# GS_01_Pow.net
KiCad netlist of a schematic drawn in Altium Designer
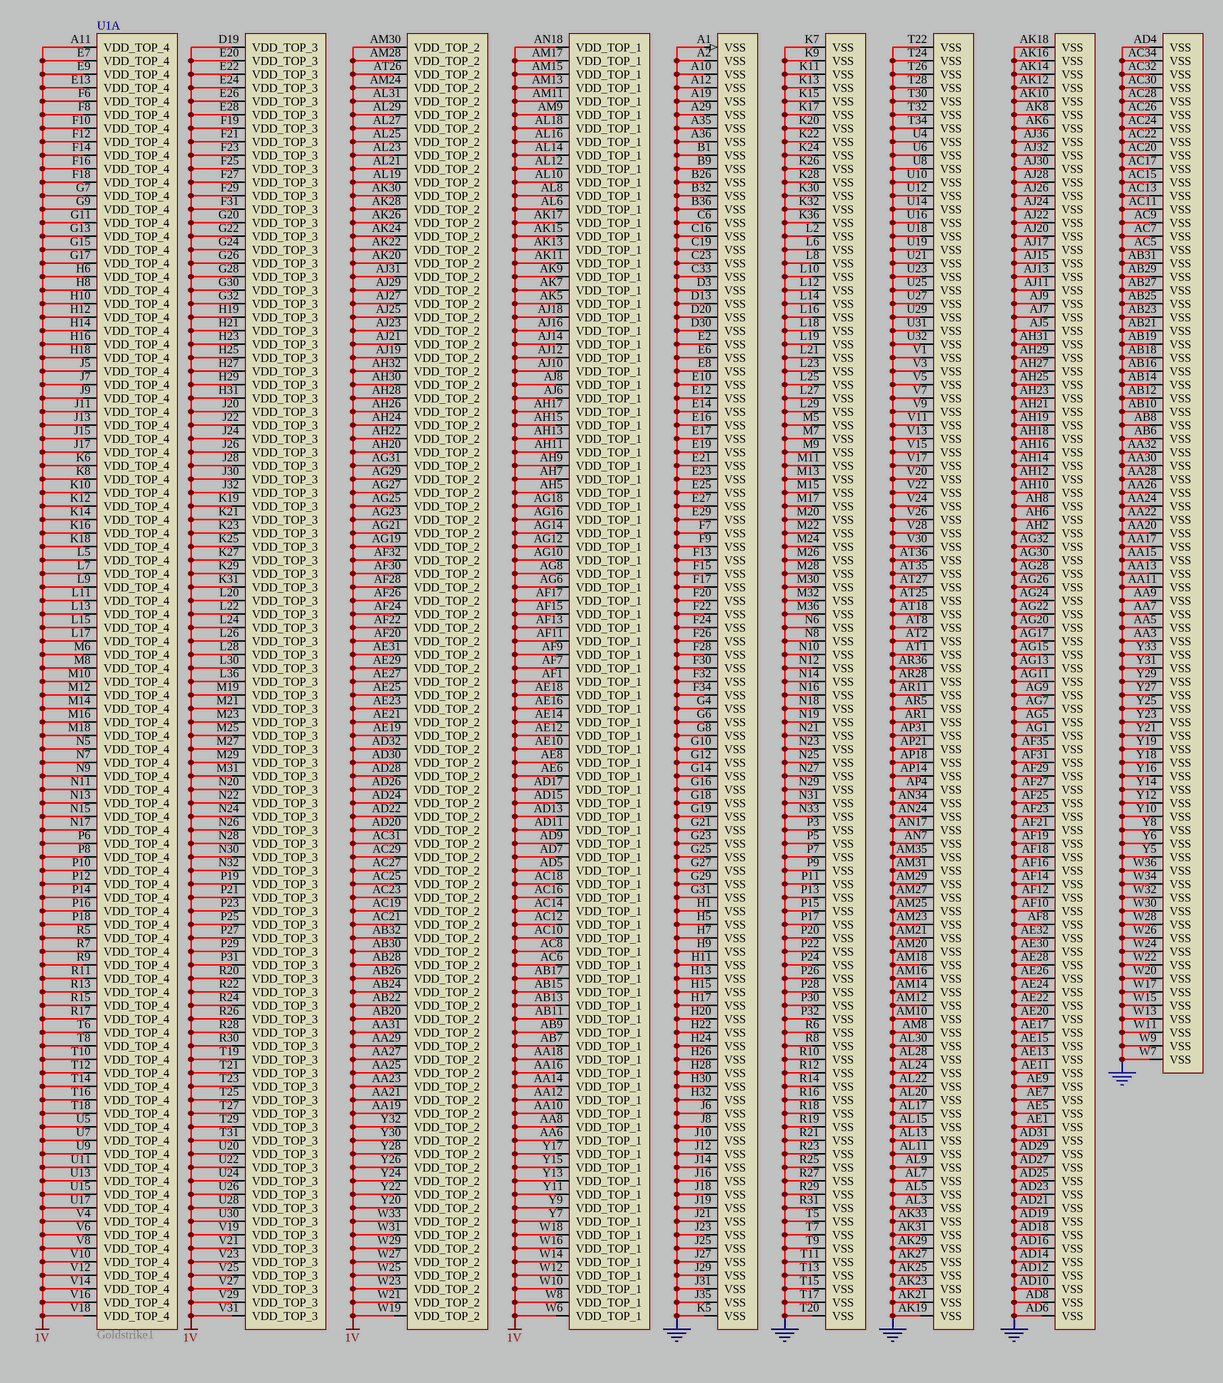
[diagram p0: GS_01_Pow.SchDoc]

(export (version "E")
  (design (tool "Eeschema 10.0.6"))
  (components (comp (ref "U1") (value "Goldstrike1") (libsource (lib "Schlib1") (part "Goldstrike1"))))
  (nets
    (net (code "1") (name "1V") (class "Default")
      (node (ref "U1") (pin "A11") (pinfunction "VDD_TOP_4_A11") (pintype "passive"))
      (node (ref "U1") (pin "AA10") (pinfunction "VDD_TOP_1_AA10") (pintype "passive"))
      (node (ref "U1") (pin "AA12") (pinfunction "VDD_TOP_1_AA12") (pintype "passive"))
      (node (ref "U1") (pin "AA14") (pinfunction "VDD_TOP_1_AA14") (pintype "passive"))
      (node (ref "U1") (pin "AA16") (pinfunction "VDD_TOP_1_AA16") (pintype "passive"))
      (node (ref "U1") (pin "AA18") (pinfunction "VDD_TOP_1_AA18") (pintype "passive"))
      (node (ref "U1") (pin "AA19") (pinfunction "VDD_TOP_2_AA19") (pintype "passive"))
      (node (ref "U1") (pin "AA21") (pinfunction "VDD_TOP_2_AA21") (pintype "passive"))
      (node (ref "U1") (pin "AA23") (pinfunction "VDD_TOP_2_AA23") (pintype "passive"))
      (node (ref "U1") (pin "AA25") (pinfunction "VDD_TOP_2_AA25") (pintype "passive"))
      (node (ref "U1") (pin "AA27") (pinfunction "VDD_TOP_2_AA27") (pintype "passive"))
      (node (ref "U1") (pin "AA29") (pinfunction "VDD_TOP_2_AA29") (pintype "passive"))
      (node (ref "U1") (pin "AA31") (pinfunction "VDD_TOP_2_AA31") (pintype "passive"))
      (node (ref "U1") (pin "AA6") (pinfunction "VDD_TOP_1_AA6") (pintype "passive"))
      (node (ref "U1") (pin "AA8") (pinfunction "VDD_TOP_1_AA8") (pintype "passive"))
      (node (ref "U1") (pin "AB11") (pinfunction "VDD_TOP_1_AB11") (pintype "passive"))
      (node (ref "U1") (pin "AB13") (pinfunction "VDD_TOP_1_AB13") (pintype "passive"))
      (node (ref "U1") (pin "AB15") (pinfunction "VDD_TOP_1_AB15") (pintype "passive"))
      (node (ref "U1") (pin "AB17") (pinfunction "VDD_TOP_1_AB17") (pintype "passive"))
      (node (ref "U1") (pin "AB20") (pinfunction "VDD_TOP_2_AB20") (pintype "passive"))
      (node (ref "U1") (pin "AB22") (pinfunction "VDD_TOP_2_AB22") (pintype "passive"))
      (node (ref "U1") (pin "AB24") (pinfunction "VDD_TOP_2_AB24") (pintype "passive"))
      (node (ref "U1") (pin "AB26") (pinfunction "VDD_TOP_2_AB26") (pintype "passive"))
      (node (ref "U1") (pin "AB28") (pinfunction "VDD_TOP_2_AB28") (pintype "passive"))
      (node (ref "U1") (pin "AB30") (pinfunction "VDD_TOP_2_AB30") (pintype "passive"))
      (node (ref "U1") (pin "AB32") (pinfunction "VDD_TOP_2_AB32") (pintype "passive"))
      (node (ref "U1") (pin "AB7") (pinfunction "VDD_TOP_1_AB7") (pintype "passive"))
      (node (ref "U1") (pin "AB9") (pinfunction "VDD_TOP_1_AB9") (pintype "passive"))
      (node (ref "U1") (pin "AC10") (pinfunction "VDD_TOP_1_AC10") (pintype "passive"))
      (node (ref "U1") (pin "AC12") (pinfunction "VDD_TOP_1_AC12") (pintype "passive"))
      (node (ref "U1") (pin "AC14") (pinfunction "VDD_TOP_1_AC14") (pintype "passive"))
      (node (ref "U1") (pin "AC16") (pinfunction "VDD_TOP_1_AC16") (pintype "passive"))
      (node (ref "U1") (pin "AC18") (pinfunction "VDD_TOP_1_AC18") (pintype "passive"))
      (node (ref "U1") (pin "AC19") (pinfunction "VDD_TOP_2_AC19") (pintype "passive"))
      (node (ref "U1") (pin "AC21") (pinfunction "VDD_TOP_2_AC21") (pintype "passive"))
      (node (ref "U1") (pin "AC23") (pinfunction "VDD_TOP_2_AC23") (pintype "passive"))
      (node (ref "U1") (pin "AC25") (pinfunction "VDD_TOP_2_AC25") (pintype "passive"))
      (node (ref "U1") (pin "AC27") (pinfunction "VDD_TOP_2_AC27") (pintype "passive"))
      (node (ref "U1") (pin "AC29") (pinfunction "VDD_TOP_2_AC29") (pintype "passive"))
      (node (ref "U1") (pin "AC31") (pinfunction "VDD_TOP_2_AC31") (pintype "passive"))
      (node (ref "U1") (pin "AC6") (pinfunction "VDD_TOP_1_AC6") (pintype "passive"))
      (node (ref "U1") (pin "AC8") (pinfunction "VDD_TOP_1_AC8") (pintype "passive"))
      (node (ref "U1") (pin "AD11") (pinfunction "VDD_TOP_1_AD11") (pintype "passive"))
      (node (ref "U1") (pin "AD13") (pinfunction "VDD_TOP_1_AD13") (pintype "passive"))
      (node (ref "U1") (pin "AD15") (pinfunction "VDD_TOP_1_AD15") (pintype "passive"))
      (node (ref "U1") (pin "AD17") (pinfunction "VDD_TOP_1_AD17") (pintype "passive"))
      (node (ref "U1") (pin "AD20") (pinfunction "VDD_TOP_2_AD20") (pintype "passive"))
      (node (ref "U1") (pin "AD22") (pinfunction "VDD_TOP_2_AD22") (pintype "passive"))
      (node (ref "U1") (pin "AD24") (pinfunction "VDD_TOP_2_AD24") (pintype "passive"))
      (node (ref "U1") (pin "AD26") (pinfunction "VDD_TOP_2_AD26") (pintype "passive"))
      (node (ref "U1") (pin "AD28") (pinfunction "VDD_TOP_2_AD28") (pintype "passive"))
      (node (ref "U1") (pin "AD30") (pinfunction "VDD_TOP_2_AD30") (pintype "passive"))
      (node (ref "U1") (pin "AD32") (pinfunction "VDD_TOP_2_AD32") (pintype "passive"))
      (node (ref "U1") (pin "AD5") (pinfunction "VDD_TOP_1_AD5") (pintype "passive"))
      (node (ref "U1") (pin "AD7") (pinfunction "VDD_TOP_1_AD7") (pintype "passive"))
      (node (ref "U1") (pin "AD9") (pinfunction "VDD_TOP_1_AD9") (pintype "passive"))
      (node (ref "U1") (pin "AE10") (pinfunction "VDD_TOP_1_AE10") (pintype "passive"))
      (node (ref "U1") (pin "AE12") (pinfunction "VDD_TOP_1_AE12") (pintype "passive"))
      (node (ref "U1") (pin "AE14") (pinfunction "VDD_TOP_1_AE14") (pintype "passive"))
      (node (ref "U1") (pin "AE16") (pinfunction "VDD_TOP_1_AE16") (pintype "passive"))
      (node (ref "U1") (pin "AE18") (pinfunction "VDD_TOP_1_AE18") (pintype "passive"))
      (node (ref "U1") (pin "AE19") (pinfunction "VDD_TOP_2_AE19") (pintype "passive"))
      (node (ref "U1") (pin "AE21") (pinfunction "VDD_TOP_2_AE21") (pintype "passive"))
      (node (ref "U1") (pin "AE23") (pinfunction "VDD_TOP_2_AE23") (pintype "passive"))
      (node (ref "U1") (pin "AE25") (pinfunction "VDD_TOP_2_AE25") (pintype "passive"))
      (node (ref "U1") (pin "AE27") (pinfunction "VDD_TOP_2_AE27") (pintype "passive"))
      (node (ref "U1") (pin "AE29") (pinfunction "VDD_TOP_2_AE29") (pintype "passive"))
      (node (ref "U1") (pin "AE31") (pinfunction "VDD_TOP_2_AE31") (pintype "passive"))
      (node (ref "U1") (pin "AE6") (pinfunction "VDD_TOP_1_AE6") (pintype "passive"))
      (node (ref "U1") (pin "AE8") (pinfunction "VDD_TOP_1_AE8") (pintype "passive"))
      (node (ref "U1") (pin "AF1") (pinfunction "VDD_TOP_1_AF1") (pintype "passive"))
      (node (ref "U1") (pin "AF11") (pinfunction "VDD_TOP_1_AF11") (pintype "passive"))
      (node (ref "U1") (pin "AF13") (pinfunction "VDD_TOP_1_AF13") (pintype "passive"))
      (node (ref "U1") (pin "AF15") (pinfunction "VDD_TOP_1_AF15") (pintype "passive"))
      (node (ref "U1") (pin "AF17") (pinfunction "VDD_TOP_1_AF17") (pintype "passive"))
      (node (ref "U1") (pin "AF20") (pinfunction "VDD_TOP_2_AF20") (pintype "passive"))
      (node (ref "U1") (pin "AF22") (pinfunction "VDD_TOP_2_AF22") (pintype "passive"))
      (node (ref "U1") (pin "AF24") (pinfunction "VDD_TOP_2_AF24") (pintype "passive"))
      (node (ref "U1") (pin "AF26") (pinfunction "VDD_TOP_2_AF26") (pintype "passive"))
      (node (ref "U1") (pin "AF28") (pinfunction "VDD_TOP_2_AF28") (pintype "passive"))
      (node (ref "U1") (pin "AF30") (pinfunction "VDD_TOP_2_AF30") (pintype "passive"))
      (node (ref "U1") (pin "AF32") (pinfunction "VDD_TOP_2_AF32") (pintype "passive"))
      (node (ref "U1") (pin "AF7") (pinfunction "VDD_TOP_1_AF7") (pintype "passive"))
      (node (ref "U1") (pin "AF9") (pinfunction "VDD_TOP_1_AF9") (pintype "passive"))
      (node (ref "U1") (pin "AG10") (pinfunction "VDD_TOP_1_AG10") (pintype "passive"))
      (node (ref "U1") (pin "AG12") (pinfunction "VDD_TOP_1_AG12") (pintype "passive"))
      (node (ref "U1") (pin "AG14") (pinfunction "VDD_TOP_1_AG14") (pintype "passive"))
      (node (ref "U1") (pin "AG16") (pinfunction "VDD_TOP_1_AG16") (pintype "passive"))
      (node (ref "U1") (pin "AG18") (pinfunction "VDD_TOP_1_AG18") (pintype "passive"))
      (node (ref "U1") (pin "AG19") (pinfunction "VDD_TOP_2_AG19") (pintype "passive"))
      (node (ref "U1") (pin "AG21") (pinfunction "VDD_TOP_2_AG21") (pintype "passive"))
      (node (ref "U1") (pin "AG23") (pinfunction "VDD_TOP_2_AG23") (pintype "passive"))
      (node (ref "U1") (pin "AG25") (pinfunction "VDD_TOP_2_AG25") (pintype "passive"))
      (node (ref "U1") (pin "AG27") (pinfunction "VDD_TOP_2_AG27") (pintype "passive"))
      (node (ref "U1") (pin "AG29") (pinfunction "VDD_TOP_2_AG29") (pintype "passive"))
      (node (ref "U1") (pin "AG31") (pinfunction "VDD_TOP_2_AG31") (pintype "passive"))
      (node (ref "U1") (pin "AG6") (pinfunction "VDD_TOP_1_AG6") (pintype "passive"))
      (node (ref "U1") (pin "AG8") (pinfunction "VDD_TOP_1_AG8") (pintype "passive"))
      (node (ref "U1") (pin "AH11") (pinfunction "VDD_TOP_1_AH11") (pintype "passive"))
      (node (ref "U1") (pin "AH13") (pinfunction "VDD_TOP_1_AH13") (pintype "passive"))
      (node (ref "U1") (pin "AH15") (pinfunction "VDD_TOP_1_AH15") (pintype "passive"))
      (node (ref "U1") (pin "AH17") (pinfunction "VDD_TOP_1_AH17") (pintype "passive"))
      (node (ref "U1") (pin "AH20") (pinfunction "VDD_TOP_2_AH20") (pintype "passive"))
      (node (ref "U1") (pin "AH22") (pinfunction "VDD_TOP_2_AH22") (pintype "passive"))
      (node (ref "U1") (pin "AH24") (pinfunction "VDD_TOP_2_AH24") (pintype "passive"))
      (node (ref "U1") (pin "AH26") (pinfunction "VDD_TOP_2_AH26") (pintype "passive"))
      (node (ref "U1") (pin "AH28") (pinfunction "VDD_TOP_2_AH28") (pintype "passive"))
      (node (ref "U1") (pin "AH30") (pinfunction "VDD_TOP_2_AH30") (pintype "passive"))
      (node (ref "U1") (pin "AH32") (pinfunction "VDD_TOP_2_AH32") (pintype "passive"))
      (node (ref "U1") (pin "AH5") (pinfunction "VDD_TOP_1_AH5") (pintype "passive"))
      (node (ref "U1") (pin "AH7") (pinfunction "VDD_TOP_1_AH7") (pintype "passive"))
      (node (ref "U1") (pin "AH9") (pinfunction "VDD_TOP_1_AH9") (pintype "passive"))
      (node (ref "U1") (pin "AJ10") (pinfunction "VDD_TOP_1_AJ10") (pintype "passive"))
      (node (ref "U1") (pin "AJ12") (pinfunction "VDD_TOP_1_AJ12") (pintype "passive"))
      (node (ref "U1") (pin "AJ14") (pinfunction "VDD_TOP_1_AJ14") (pintype "passive"))
      (node (ref "U1") (pin "AJ16") (pinfunction "VDD_TOP_1_AJ16") (pintype "passive"))
      (node (ref "U1") (pin "AJ18") (pinfunction "VDD_TOP_1_AJ18") (pintype "passive"))
      (node (ref "U1") (pin "AJ19") (pinfunction "VDD_TOP_2_AJ19") (pintype "passive"))
      (node (ref "U1") (pin "AJ21") (pinfunction "VDD_TOP_2_AJ21") (pintype "passive"))
      (node (ref "U1") (pin "AJ23") (pinfunction "VDD_TOP_2_AJ23") (pintype "passive"))
      (node (ref "U1") (pin "AJ25") (pinfunction "VDD_TOP_2_AJ25") (pintype "passive"))
      (node (ref "U1") (pin "AJ27") (pinfunction "VDD_TOP_2_AJ27") (pintype "passive"))
      (node (ref "U1") (pin "AJ29") (pinfunction "VDD_TOP_2_AJ29") (pintype "passive"))
      (node (ref "U1") (pin "AJ31") (pinfunction "VDD_TOP_2_AJ31") (pintype "passive"))
      (node (ref "U1") (pin "AJ6") (pinfunction "VDD_TOP_1_AJ6") (pintype "passive"))
      (node (ref "U1") (pin "AJ8") (pinfunction "VDD_TOP_1_AJ8") (pintype "passive"))
      (node (ref "U1") (pin "AK11") (pinfunction "VDD_TOP_1_AK11") (pintype "passive"))
      (node (ref "U1") (pin "AK13") (pinfunction "VDD_TOP_1_AK13") (pintype "passive"))
      (node (ref "U1") (pin "AK15") (pinfunction "VDD_TOP_1_AK15") (pintype "passive"))
      (node (ref "U1") (pin "AK17") (pinfunction "VDD_TOP_1_AK17") (pintype "passive"))
      (node (ref "U1") (pin "AK20") (pinfunction "VDD_TOP_2_AK20") (pintype "passive"))
      (node (ref "U1") (pin "AK22") (pinfunction "VDD_TOP_2_AK22") (pintype "passive"))
      (node (ref "U1") (pin "AK24") (pinfunction "VDD_TOP_2_AK24") (pintype "passive"))
      (node (ref "U1") (pin "AK26") (pinfunction "VDD_TOP_2_AK26") (pintype "passive"))
      (node (ref "U1") (pin "AK28") (pinfunction "VDD_TOP_2_AK28") (pintype "passive"))
      (node (ref "U1") (pin "AK30") (pinfunction "VDD_TOP_2_AK30") (pintype "passive"))
      (node (ref "U1") (pin "AK5") (pinfunction "VDD_TOP_1_AK5") (pintype "passive"))
      (node (ref "U1") (pin "AK7") (pinfunction "VDD_TOP_1_AK7") (pintype "passive"))
      (node (ref "U1") (pin "AK9") (pinfunction "VDD_TOP_1_AK9") (pintype "passive"))
      (node (ref "U1") (pin "AL10") (pinfunction "VDD_TOP_1_AL10") (pintype "passive"))
      (node (ref "U1") (pin "AL12") (pinfunction "VDD_TOP_1_AL12") (pintype "passive"))
      (node (ref "U1") (pin "AL14") (pinfunction "VDD_TOP_1_AL14") (pintype "passive"))
      (node (ref "U1") (pin "AL16") (pinfunction "VDD_TOP_1_AL16") (pintype "passive"))
      (node (ref "U1") (pin "AL18") (pinfunction "VDD_TOP_1_AL18") (pintype "passive"))
      (node (ref "U1") (pin "AL19") (pinfunction "VDD_TOP_2_AL19") (pintype "passive"))
      (node (ref "U1") (pin "AL21") (pinfunction "VDD_TOP_2_AL21") (pintype "passive"))
      (node (ref "U1") (pin "AL23") (pinfunction "VDD_TOP_2_AL23") (pintype "passive"))
      (node (ref "U1") (pin "AL25") (pinfunction "VDD_TOP_2_AL25") (pintype "passive"))
      (node (ref "U1") (pin "AL27") (pinfunction "VDD_TOP_2_AL27") (pintype "passive"))
      (node (ref "U1") (pin "AL29") (pinfunction "VDD_TOP_2_AL29") (pintype "passive"))
      (node (ref "U1") (pin "AL31") (pinfunction "VDD_TOP_2_AL31") (pintype "passive"))
      (node (ref "U1") (pin "AL6") (pinfunction "VDD_TOP_1_AL6") (pintype "passive"))
      (node (ref "U1") (pin "AL8") (pinfunction "VDD_TOP_1_AL8") (pintype "passive"))
      (node (ref "U1") (pin "AM11") (pinfunction "VDD_TOP_1_AM11") (pintype "passive"))
      (node (ref "U1") (pin "AM13") (pinfunction "VDD_TOP_1_AM13") (pintype "passive"))
      (node (ref "U1") (pin "AM15") (pinfunction "VDD_TOP_1_AM15") (pintype "passive"))
      (node (ref "U1") (pin "AM17") (pinfunction "VDD_TOP_1_AM17") (pintype "passive"))
      (node (ref "U1") (pin "AM24") (pinfunction "VDD_TOP_2_AM24") (pintype "passive"))
      (node (ref "U1") (pin "AM28") (pinfunction "VDD_TOP_2_AM28") (pintype "passive"))
      (node (ref "U1") (pin "AM30") (pinfunction "VDD_TOP_2_AM30") (pintype "passive"))
      (node (ref "U1") (pin "AM9") (pinfunction "VDD_TOP_1_AM9") (pintype "passive"))
      (node (ref "U1") (pin "AN18") (pinfunction "VDD_TOP_1_AN18") (pintype "passive"))
      (node (ref "U1") (pin "AT26") (pinfunction "VDD_TOP_2_AT26") (pintype "passive"))
      (node (ref "U1") (pin "D19") (pinfunction "VDD_TOP_3_D19") (pintype "passive"))
      (node (ref "U1") (pin "E13") (pinfunction "VDD_TOP_4_E13") (pintype "passive"))
      (node (ref "U1") (pin "E20") (pinfunction "VDD_TOP_3_E20") (pintype "passive"))
      (node (ref "U1") (pin "E22") (pinfunction "VDD_TOP_3_E22") (pintype "passive"))
      (node (ref "U1") (pin "E24") (pinfunction "VDD_TOP_3_E24") (pintype "passive"))
      (node (ref "U1") (pin "E26") (pinfunction "VDD_TOP_3_E26") (pintype "passive"))
      (node (ref "U1") (pin "E28") (pinfunction "VDD_TOP_3_E28") (pintype "passive"))
      (node (ref "U1") (pin "E7") (pinfunction "VDD_TOP_4_E7") (pintype "passive"))
      (node (ref "U1") (pin "E9") (pinfunction "VDD_TOP_4_E9") (pintype "passive"))
      (node (ref "U1") (pin "F10") (pinfunction "VDD_TOP_4_F10") (pintype "passive"))
      (node (ref "U1") (pin "F12") (pinfunction "VDD_TOP_4_F12") (pintype "passive"))
      (node (ref "U1") (pin "F14") (pinfunction "VDD_TOP_4_F14") (pintype "passive"))
      (node (ref "U1") (pin "F16") (pinfunction "VDD_TOP_4_F16") (pintype "passive"))
      (node (ref "U1") (pin "F18") (pinfunction "VDD_TOP_4_F18") (pintype "passive"))
      (node (ref "U1") (pin "F19") (pinfunction "VDD_TOP_3_F19") (pintype "passive"))
      (node (ref "U1") (pin "F21") (pinfunction "VDD_TOP_3_F21") (pintype "passive"))
      (node (ref "U1") (pin "F23") (pinfunction "VDD_TOP_3_F23") (pintype "passive"))
      (node (ref "U1") (pin "F25") (pinfunction "VDD_TOP_3_F25") (pintype "passive"))
      (node (ref "U1") (pin "F27") (pinfunction "VDD_TOP_3_F27") (pintype "passive"))
      (node (ref "U1") (pin "F29") (pinfunction "VDD_TOP_3_F29") (pintype "passive"))
      (node (ref "U1") (pin "F31") (pinfunction "VDD_TOP_3_F31") (pintype "passive"))
      (node (ref "U1") (pin "F6") (pinfunction "VDD_TOP_4_F6") (pintype "passive"))
      (node (ref "U1") (pin "F8") (pinfunction "VDD_TOP_4_F8") (pintype "passive"))
      (node (ref "U1") (pin "G11") (pinfunction "VDD_TOP_4_G11") (pintype "passive"))
      (node (ref "U1") (pin "G13") (pinfunction "VDD_TOP_4_G13") (pintype "passive"))
      (node (ref "U1") (pin "G15") (pinfunction "VDD_TOP_4_G15") (pintype "passive"))
      (node (ref "U1") (pin "G17") (pinfunction "VDD_TOP_4_G17") (pintype "passive"))
      (node (ref "U1") (pin "G20") (pinfunction "VDD_TOP_3_G20") (pintype "passive"))
      (node (ref "U1") (pin "G22") (pinfunction "VDD_TOP_3_G22") (pintype "passive"))
      (node (ref "U1") (pin "G24") (pinfunction "VDD_TOP_3_G24") (pintype "passive"))
      (node (ref "U1") (pin "G26") (pinfunction "VDD_TOP_3_G26") (pintype "passive"))
      (node (ref "U1") (pin "G28") (pinfunction "VDD_TOP_3_G28") (pintype "passive"))
      (node (ref "U1") (pin "G30") (pinfunction "VDD_TOP_3_G30") (pintype "passive"))
      (node (ref "U1") (pin "G32") (pinfunction "VDD_TOP_3_G32") (pintype "passive"))
      (node (ref "U1") (pin "G7") (pinfunction "VDD_TOP_4_G7") (pintype "passive"))
      (node (ref "U1") (pin "G9") (pinfunction "VDD_TOP_4_G9") (pintype "passive"))
      (node (ref "U1") (pin "H10") (pinfunction "VDD_TOP_4_H10") (pintype "passive"))
      (node (ref "U1") (pin "H12") (pinfunction "VDD_TOP_4_H12") (pintype "passive"))
      (node (ref "U1") (pin "H14") (pinfunction "VDD_TOP_4_H14") (pintype "passive"))
      (node (ref "U1") (pin "H16") (pinfunction "VDD_TOP_4_H16") (pintype "passive"))
      (node (ref "U1") (pin "H18") (pinfunction "VDD_TOP_4_H18") (pintype "passive"))
      (node (ref "U1") (pin "H19") (pinfunction "VDD_TOP_3_H19") (pintype "passive"))
      (node (ref "U1") (pin "H21") (pinfunction "VDD_TOP_3_H21") (pintype "passive"))
      (node (ref "U1") (pin "H23") (pinfunction "VDD_TOP_3_H23") (pintype "passive"))
      (node (ref "U1") (pin "H25") (pinfunction "VDD_TOP_3_H25") (pintype "passive"))
      (node (ref "U1") (pin "H27") (pinfunction "VDD_TOP_3_H27") (pintype "passive"))
      (node (ref "U1") (pin "H29") (pinfunction "VDD_TOP_3_H29") (pintype "passive"))
      (node (ref "U1") (pin "H31") (pinfunction "VDD_TOP_3_H31") (pintype "passive"))
      (node (ref "U1") (pin "H6") (pinfunction "VDD_TOP_4_H6") (pintype "passive"))
      (node (ref "U1") (pin "H8") (pinfunction "VDD_TOP_4_H8") (pintype "passive"))
      (node (ref "U1") (pin "J11") (pinfunction "VDD_TOP_4_J11") (pintype "passive"))
      (node (ref "U1") (pin "J13") (pinfunction "VDD_TOP_4_J13") (pintype "passive"))
      (node (ref "U1") (pin "J15") (pinfunction "VDD_TOP_4_J15") (pintype "passive"))
      (node (ref "U1") (pin "J17") (pinfunction "VDD_TOP_4_J17") (pintype "passive"))
      (node (ref "U1") (pin "J20") (pinfunction "VDD_TOP_3_J20") (pintype "passive"))
      (node (ref "U1") (pin "J22") (pinfunction "VDD_TOP_3_J22") (pintype "passive"))
      (node (ref "U1") (pin "J24") (pinfunction "VDD_TOP_3_J24") (pintype "passive"))
      (node (ref "U1") (pin "J26") (pinfunction "VDD_TOP_3_J26") (pintype "passive"))
      (node (ref "U1") (pin "J28") (pinfunction "VDD_TOP_3_J28") (pintype "passive"))
      (node (ref "U1") (pin "J30") (pinfunction "VDD_TOP_3_J30") (pintype "passive"))
      (node (ref "U1") (pin "J32") (pinfunction "VDD_TOP_3_J32") (pintype "passive"))
      (node (ref "U1") (pin "J5") (pinfunction "VDD_TOP_4_J5") (pintype "passive"))
      (node (ref "U1") (pin "J7") (pinfunction "VDD_TOP_4_J7") (pintype "passive"))
      (node (ref "U1") (pin "J9") (pinfunction "VDD_TOP_4_J9") (pintype "passive"))
      (node (ref "U1") (pin "K10") (pinfunction "VDD_TOP_4_K10") (pintype "passive"))
      (node (ref "U1") (pin "K12") (pinfunction "VDD_TOP_4_K12") (pintype "passive"))
      (node (ref "U1") (pin "K14") (pinfunction "VDD_TOP_4_K14") (pintype "passive"))
      (node (ref "U1") (pin "K16") (pinfunction "VDD_TOP_4_K16") (pintype "passive"))
      (node (ref "U1") (pin "K18") (pinfunction "VDD_TOP_4_K18") (pintype "passive"))
      (node (ref "U1") (pin "K19") (pinfunction "VDD_TOP_3_K19") (pintype "passive"))
      (node (ref "U1") (pin "K21") (pinfunction "VDD_TOP_3_K21") (pintype "passive"))
      (node (ref "U1") (pin "K23") (pinfunction "VDD_TOP_3_K23") (pintype "passive"))
      (node (ref "U1") (pin "K25") (pinfunction "VDD_TOP_3_K25") (pintype "passive"))
      (node (ref "U1") (pin "K27") (pinfunction "VDD_TOP_3_K27") (pintype "passive"))
      (node (ref "U1") (pin "K29") (pinfunction "VDD_TOP_3_K29") (pintype "passive"))
      (node (ref "U1") (pin "K31") (pinfunction "VDD_TOP_3_K31") (pintype "passive"))
      (node (ref "U1") (pin "K6") (pinfunction "VDD_TOP_4_K6") (pintype "passive"))
      (node (ref "U1") (pin "K8") (pinfunction "VDD_TOP_4_K8") (pintype "passive"))
      (node (ref "U1") (pin "L11") (pinfunction "VDD_TOP_4_L11") (pintype "passive"))
      (node (ref "U1") (pin "L13") (pinfunction "VDD_TOP_4_L13") (pintype "passive"))
      (node (ref "U1") (pin "L15") (pinfunction "VDD_TOP_4_L15") (pintype "passive"))
      (node (ref "U1") (pin "L17") (pinfunction "VDD_TOP_4_L17") (pintype "passive"))
      (node (ref "U1") (pin "L20") (pinfunction "VDD_TOP_3_L20") (pintype "passive"))
      (node (ref "U1") (pin "L22") (pinfunction "VDD_TOP_3_L22") (pintype "passive"))
      (node (ref "U1") (pin "L24") (pinfunction "VDD_TOP_3_L24") (pintype "passive"))
      (node (ref "U1") (pin "L26") (pinfunction "VDD_TOP_3_L26") (pintype "passive"))
      (node (ref "U1") (pin "L28") (pinfunction "VDD_TOP_3_L28") (pintype "passive"))
      (node (ref "U1") (pin "L30") (pinfunction "VDD_TOP_3_L30") (pintype "passive"))
      (node (ref "U1") (pin "L36") (pinfunction "VDD_TOP_3_L36") (pintype "passive"))
      (node (ref "U1") (pin "L5") (pinfunction "VDD_TOP_4_L5") (pintype "passive"))
      (node (ref "U1") (pin "L7") (pinfunction "VDD_TOP_4_L7") (pintype "passive"))
      (node (ref "U1") (pin "L9") (pinfunction "VDD_TOP_4_L9") (pintype "passive"))
      (node (ref "U1") (pin "M10") (pinfunction "VDD_TOP_4_M10") (pintype "passive"))
      (node (ref "U1") (pin "M12") (pinfunction "VDD_TOP_4_M12") (pintype "passive"))
      (node (ref "U1") (pin "M14") (pinfunction "VDD_TOP_4_M14") (pintype "passive"))
      (node (ref "U1") (pin "M16") (pinfunction "VDD_TOP_4_M16") (pintype "passive"))
      (node (ref "U1") (pin "M18") (pinfunction "VDD_TOP_4_M18") (pintype "passive"))
      (node (ref "U1") (pin "M19") (pinfunction "VDD_TOP_3_M19") (pintype "passive"))
      (node (ref "U1") (pin "M21") (pinfunction "VDD_TOP_3_M21") (pintype "passive"))
      (node (ref "U1") (pin "M23") (pinfunction "VDD_TOP_3_M23") (pintype "passive"))
      (node (ref "U1") (pin "M25") (pinfunction "VDD_TOP_3_M25") (pintype "passive"))
      (node (ref "U1") (pin "M27") (pinfunction "VDD_TOP_3_M27") (pintype "passive"))
      (node (ref "U1") (pin "M29") (pinfunction "VDD_TOP_3_M29") (pintype "passive"))
      (node (ref "U1") (pin "M31") (pinfunction "VDD_TOP_3_M31") (pintype "passive"))
      (node (ref "U1") (pin "M6") (pinfunction "VDD_TOP_4_M6") (pintype "passive"))
      (node (ref "U1") (pin "M8") (pinfunction "VDD_TOP_4_M8") (pintype "passive"))
      (node (ref "U1") (pin "N11") (pinfunction "VDD_TOP_4_N11") (pintype "passive"))
      (node (ref "U1") (pin "N13") (pinfunction "VDD_TOP_4_N13") (pintype "passive"))
      (node (ref "U1") (pin "N15") (pinfunction "VDD_TOP_4_N15") (pintype "passive"))
      (node (ref "U1") (pin "N17") (pinfunction "VDD_TOP_4_N17") (pintype "passive"))
      (node (ref "U1") (pin "N20") (pinfunction "VDD_TOP_3_N20") (pintype "passive"))
      (node (ref "U1") (pin "N22") (pinfunction "VDD_TOP_3_N22") (pintype "passive"))
      (node (ref "U1") (pin "N24") (pinfunction "VDD_TOP_3_N24") (pintype "passive"))
      (node (ref "U1") (pin "N26") (pinfunction "VDD_TOP_3_N26") (pintype "passive"))
      (node (ref "U1") (pin "N28") (pinfunction "VDD_TOP_3_N28") (pintype "passive"))
      (node (ref "U1") (pin "N30") (pinfunction "VDD_TOP_3_N30") (pintype "passive"))
      (node (ref "U1") (pin "N32") (pinfunction "VDD_TOP_3_N32") (pintype "passive"))
      (node (ref "U1") (pin "N5") (pinfunction "VDD_TOP_4_N5") (pintype "passive"))
      (node (ref "U1") (pin "N7") (pinfunction "VDD_TOP_4_N7") (pintype "passive"))
      (node (ref "U1") (pin "N9") (pinfunction "VDD_TOP_4_N9") (pintype "passive"))
      (node (ref "U1") (pin "P10") (pinfunction "VDD_TOP_4_P10") (pintype "passive"))
      (node (ref "U1") (pin "P12") (pinfunction "VDD_TOP_4_P12") (pintype "passive"))
      (node (ref "U1") (pin "P14") (pinfunction "VDD_TOP_4_P14") (pintype "passive"))
      (node (ref "U1") (pin "P16") (pinfunction "VDD_TOP_4_P16") (pintype "passive"))
      (node (ref "U1") (pin "P18") (pinfunction "VDD_TOP_4_P18") (pintype "passive"))
      (node (ref "U1") (pin "P19") (pinfunction "VDD_TOP_3_P19") (pintype "passive"))
      (node (ref "U1") (pin "P21") (pinfunction "VDD_TOP_3_P21") (pintype "passive"))
      (node (ref "U1") (pin "P23") (pinfunction "VDD_TOP_3_P23") (pintype "passive"))
      (node (ref "U1") (pin "P25") (pinfunction "VDD_TOP_3_P25") (pintype "passive"))
      (node (ref "U1") (pin "P27") (pinfunction "VDD_TOP_3_P27") (pintype "passive"))
      (node (ref "U1") (pin "P29") (pinfunction "VDD_TOP_3_P29") (pintype "passive"))
      (node (ref "U1") (pin "P31") (pinfunction "VDD_TOP_3_P31") (pintype "passive"))
      (node (ref "U1") (pin "P6") (pinfunction "VDD_TOP_4_P6") (pintype "passive"))
      (node (ref "U1") (pin "P8") (pinfunction "VDD_TOP_4_P8") (pintype "passive"))
      (node (ref "U1") (pin "R11") (pinfunction "VDD_TOP_4_R11") (pintype "passive"))
      (node (ref "U1") (pin "R13") (pinfunction "VDD_TOP_4_R13") (pintype "passive"))
      (node (ref "U1") (pin "R15") (pinfunction "VDD_TOP_4_R15") (pintype "passive"))
      (node (ref "U1") (pin "R17") (pinfunction "VDD_TOP_4_R17") (pintype "passive"))
      (node (ref "U1") (pin "R20") (pinfunction "VDD_TOP_3_R20") (pintype "passive"))
      (node (ref "U1") (pin "R22") (pinfunction "VDD_TOP_3_R22") (pintype "passive"))
      (node (ref "U1") (pin "R24") (pinfunction "VDD_TOP_3_R24") (pintype "passive"))
      (node (ref "U1") (pin "R26") (pinfunction "VDD_TOP_3_R26") (pintype "passive"))
      (node (ref "U1") (pin "R28") (pinfunction "VDD_TOP_3_R28") (pintype "passive"))
      (node (ref "U1") (pin "R30") (pinfunction "VDD_TOP_3_R30") (pintype "passive"))
      (node (ref "U1") (pin "R5") (pinfunction "VDD_TOP_4_R5") (pintype "passive"))
      (node (ref "U1") (pin "R7") (pinfunction "VDD_TOP_4_R7") (pintype "passive"))
      (node (ref "U1") (pin "R9") (pinfunction "VDD_TOP_4_R9") (pintype "passive"))
      (node (ref "U1") (pin "T10") (pinfunction "VDD_TOP_4_T10") (pintype "passive"))
      (node (ref "U1") (pin "T12") (pinfunction "VDD_TOP_4_T12") (pintype "passive"))
      (node (ref "U1") (pin "T14") (pinfunction "VDD_TOP_4_T14") (pintype "passive"))
      (node (ref "U1") (pin "T16") (pinfunction "VDD_TOP_4_T16") (pintype "passive"))
      (node (ref "U1") (pin "T18") (pinfunction "VDD_TOP_4_T18") (pintype "passive"))
      (node (ref "U1") (pin "T19") (pinfunction "VDD_TOP_3_T19") (pintype "passive"))
      (node (ref "U1") (pin "T21") (pinfunction "VDD_TOP_3_T21") (pintype "passive"))
      (node (ref "U1") (pin "T23") (pinfunction "VDD_TOP_3_T23") (pintype "passive"))
      (node (ref "U1") (pin "T25") (pinfunction "VDD_TOP_3_T25") (pintype "passive"))
      (node (ref "U1") (pin "T27") (pinfunction "VDD_TOP_3_T27") (pintype "passive"))
      (node (ref "U1") (pin "T29") (pinfunction "VDD_TOP_3_T29") (pintype "passive"))
      (node (ref "U1") (pin "T31") (pinfunction "VDD_TOP_3_T31") (pintype "passive"))
      (node (ref "U1") (pin "T6") (pinfunction "VDD_TOP_4_T6") (pintype "passive"))
      (node (ref "U1") (pin "T8") (pinfunction "VDD_TOP_4_T8") (pintype "passive"))
      (node (ref "U1") (pin "U11") (pinfunction "VDD_TOP_4_U11") (pintype "passive"))
      (node (ref "U1") (pin "U13") (pinfunction "VDD_TOP_4_U13") (pintype "passive"))
      (node (ref "U1") (pin "U15") (pinfunction "VDD_TOP_4_U15") (pintype "passive"))
      (node (ref "U1") (pin "U17") (pinfunction "VDD_TOP_4_U17") (pintype "passive"))
      (node (ref "U1") (pin "U20") (pinfunction "VDD_TOP_3_U20") (pintype "passive"))
      (node (ref "U1") (pin "U22") (pinfunction "VDD_TOP_3_U22") (pintype "passive"))
      (node (ref "U1") (pin "U24") (pinfunction "VDD_TOP_3_U24") (pintype "passive"))
      (node (ref "U1") (pin "U26") (pinfunction "VDD_TOP_3_U26") (pintype "passive"))
      (node (ref "U1") (pin "U28") (pinfunction "VDD_TOP_3_U28") (pintype "passive"))
      (node (ref "U1") (pin "U30") (pinfunction "VDD_TOP_3_U30") (pintype "passive"))
      (node (ref "U1") (pin "U5") (pinfunction "VDD_TOP_4_U5") (pintype "passive"))
      (node (ref "U1") (pin "U7") (pinfunction "VDD_TOP_4_U7") (pintype "passive"))
      (node (ref "U1") (pin "U9") (pinfunction "VDD_TOP_4_U9") (pintype "passive"))
      (node (ref "U1") (pin "V10") (pinfunction "VDD_TOP_4_V10") (pintype "passive"))
      (node (ref "U1") (pin "V12") (pinfunction "VDD_TOP_4_V12") (pintype "passive"))
      (node (ref "U1") (pin "V14") (pinfunction "VDD_TOP_4_V14") (pintype "passive"))
      (node (ref "U1") (pin "V16") (pinfunction "VDD_TOP_4_V16") (pintype "passive"))
      (node (ref "U1") (pin "V18") (pinfunction "VDD_TOP_4_V18") (pintype "passive"))
      (node (ref "U1") (pin "V19") (pinfunction "VDD_TOP_3_V19") (pintype "passive"))
      (node (ref "U1") (pin "V21") (pinfunction "VDD_TOP_3_V21") (pintype "passive"))
      (node (ref "U1") (pin "V23") (pinfunction "VDD_TOP_3_V23") (pintype "passive"))
      (node (ref "U1") (pin "V25") (pinfunction "VDD_TOP_3_V25") (pintype "passive"))
      (node (ref "U1") (pin "V27") (pinfunction "VDD_TOP_3_V27") (pintype "passive"))
      (node (ref "U1") (pin "V29") (pinfunction "VDD_TOP_3_V29") (pintype "passive"))
      (node (ref "U1") (pin "V31") (pinfunction "VDD_TOP_3_V31") (pintype "passive"))
      (node (ref "U1") (pin "V4") (pinfunction "VDD_TOP_4_V4") (pintype "passive"))
      (node (ref "U1") (pin "V6") (pinfunction "VDD_TOP_4_V6") (pintype "passive"))
      (node (ref "U1") (pin "V8") (pinfunction "VDD_TOP_4_V8") (pintype "passive"))
      (node (ref "U1") (pin "W10") (pinfunction "VDD_TOP_1_W10") (pintype "passive"))
      (node (ref "U1") (pin "W12") (pinfunction "VDD_TOP_1_W12") (pintype "passive"))
      (node (ref "U1") (pin "W14") (pinfunction "VDD_TOP_1_W14") (pintype "passive"))
      (node (ref "U1") (pin "W16") (pinfunction "VDD_TOP_1_W16") (pintype "passive"))
      (node (ref "U1") (pin "W18") (pinfunction "VDD_TOP_1_W18") (pintype "passive"))
      (node (ref "U1") (pin "W19") (pinfunction "VDD_TOP_2_W19") (pintype "passive"))
      (node (ref "U1") (pin "W21") (pinfunction "VDD_TOP_2_W21") (pintype "passive"))
      (node (ref "U1") (pin "W23") (pinfunction "VDD_TOP_2_W23") (pintype "passive"))
      (node (ref "U1") (pin "W25") (pinfunction "VDD_TOP_2_W25") (pintype "passive"))
      (node (ref "U1") (pin "W27") (pinfunction "VDD_TOP_2_W27") (pintype "passive"))
      (node (ref "U1") (pin "W29") (pinfunction "VDD_TOP_2_W29") (pintype "passive"))
      (node (ref "U1") (pin "W31") (pinfunction "VDD_TOP_2_W31") (pintype "passive"))
      (node (ref "U1") (pin "W33") (pinfunction "VDD_TOP_2_W33") (pintype "passive"))
      (node (ref "U1") (pin "W6") (pinfunction "VDD_TOP_1_W6") (pintype "passive"))
      (node (ref "U1") (pin "W8") (pinfunction "VDD_TOP_1_W8") (pintype "passive"))
      (node (ref "U1") (pin "Y11") (pinfunction "VDD_TOP_1_Y11") (pintype "passive"))
      (node (ref "U1") (pin "Y13") (pinfunction "VDD_TOP_1_Y13") (pintype "passive"))
      (node (ref "U1") (pin "Y15") (pinfunction "VDD_TOP_1_Y15") (pintype "passive"))
      (node (ref "U1") (pin "Y17") (pinfunction "VDD_TOP_1_Y17") (pintype "passive"))
      (node (ref "U1") (pin "Y20") (pinfunction "VDD_TOP_2_Y20") (pintype "passive"))
      (node (ref "U1") (pin "Y22") (pinfunction "VDD_TOP_2_Y22") (pintype "passive"))
      (node (ref "U1") (pin "Y24") (pinfunction "VDD_TOP_2_Y24") (pintype "passive"))
      (node (ref "U1") (pin "Y26") (pinfunction "VDD_TOP_2_Y26") (pintype "passive"))
      (node (ref "U1") (pin "Y28") (pinfunction "VDD_TOP_2_Y28") (pintype "passive"))
      (node (ref "U1") (pin "Y30") (pinfunction "VDD_TOP_2_Y30") (pintype "passive"))
      (node (ref "U1") (pin "Y32") (pinfunction "VDD_TOP_2_Y32") (pintype "passive"))
      (node (ref "U1") (pin "Y7") (pinfunction "VDD_TOP_1_Y7") (pintype "passive"))
      (node (ref "U1") (pin "Y9") (pinfunction "VDD_TOP_1_Y9") (pintype "passive"))
    )
    (net (code "2") (name "GND") (class "Default")
      (node (ref "U1") (pin "A1") (pinfunction "VSS_A1") (pintype "input"))
      (node (ref "U1") (pin "A10") (pinfunction "VSS_A10") (pintype "passive"))
      (node (ref "U1") (pin "A12") (pinfunction "VSS_A12") (pintype "passive"))
      (node (ref "U1") (pin "A19") (pinfunction "VSS_A19") (pintype "passive"))
      (node (ref "U1") (pin "A2") (pinfunction "VSS_A2") (pintype "passive"))
      (node (ref "U1") (pin "A29") (pinfunction "VSS_A29") (pintype "passive"))
      (node (ref "U1") (pin "A35") (pinfunction "VSS_A35") (pintype "passive"))
      (node (ref "U1") (pin "A36") (pinfunction "VSS_A36") (pintype "passive"))
      (node (ref "U1") (pin "AA11") (pinfunction "VSS_AA11") (pintype "passive"))
      (node (ref "U1") (pin "AA13") (pinfunction "VSS_AA13") (pintype "passive"))
      (node (ref "U1") (pin "AA15") (pinfunction "VSS_AA15") (pintype "passive"))
      (node (ref "U1") (pin "AA17") (pinfunction "VSS_AA17") (pintype "passive"))
      (node (ref "U1") (pin "AA20") (pinfunction "VSS_AA20") (pintype "passive"))
      (node (ref "U1") (pin "AA22") (pinfunction "VSS_AA22") (pintype "passive"))
      (node (ref "U1") (pin "AA24") (pinfunction "VSS_AA24") (pintype "passive"))
      (node (ref "U1") (pin "AA26") (pinfunction "VSS_AA26") (pintype "passive"))
      (node (ref "U1") (pin "AA28") (pinfunction "VSS_AA28") (pintype "passive"))
      (node (ref "U1") (pin "AA3") (pinfunction "VSS_AA3") (pintype "passive"))
      (node (ref "U1") (pin "AA30") (pinfunction "VSS_AA30") (pintype "passive"))
      (node (ref "U1") (pin "AA32") (pinfunction "VSS_AA32") (pintype "passive"))
      (node (ref "U1") (pin "AA5") (pinfunction "VSS_AA5") (pintype "passive"))
      (node (ref "U1") (pin "AA7") (pinfunction "VSS_AA7") (pintype "passive"))
      (node (ref "U1") (pin "AA9") (pinfunction "VSS_AA9") (pintype "passive"))
      (node (ref "U1") (pin "AB10") (pinfunction "VSS_AB10") (pintype "passive"))
      (node (ref "U1") (pin "AB12") (pinfunction "VSS_AB12") (pintype "passive"))
      (node (ref "U1") (pin "AB14") (pinfunction "VSS_AB14") (pintype "passive"))
      (node (ref "U1") (pin "AB16") (pinfunction "VSS_AB16") (pintype "passive"))
      (node (ref "U1") (pin "AB18") (pinfunction "VSS_AB18") (pintype "passive"))
      (node (ref "U1") (pin "AB19") (pinfunction "VSS_AB19") (pintype "passive"))
      (node (ref "U1") (pin "AB21") (pinfunction "VSS_AB21") (pintype "passive"))
      (node (ref "U1") (pin "AB23") (pinfunction "VSS_AB23") (pintype "passive"))
      (node (ref "U1") (pin "AB25") (pinfunction "VSS_AB25") (pintype "passive"))
      (node (ref "U1") (pin "AB27") (pinfunction "VSS_AB27") (pintype "passive"))
      (node (ref "U1") (pin "AB29") (pinfunction "VSS_AB29") (pintype "passive"))
      (node (ref "U1") (pin "AB31") (pinfunction "VSS_AB31") (pintype "passive"))
      (node (ref "U1") (pin "AB6") (pinfunction "VSS_AB6") (pintype "passive"))
      (node (ref "U1") (pin "AB8") (pinfunction "VSS_AB8") (pintype "passive"))
      (node (ref "U1") (pin "AC11") (pinfunction "VSS_AC11") (pintype "passive"))
      (node (ref "U1") (pin "AC13") (pinfunction "VSS_AC13") (pintype "passive"))
      (node (ref "U1") (pin "AC15") (pinfunction "VSS_AC15") (pintype "passive"))
      (node (ref "U1") (pin "AC17") (pinfunction "VSS_AC17") (pintype "passive"))
      (node (ref "U1") (pin "AC20") (pinfunction "VSS_AC20") (pintype "passive"))
      (node (ref "U1") (pin "AC22") (pinfunction "VSS_AC22") (pintype "passive"))
      (node (ref "U1") (pin "AC24") (pinfunction "VSS_AC24") (pintype "passive"))
      (node (ref "U1") (pin "AC26") (pinfunction "VSS_AC26") (pintype "passive"))
      (node (ref "U1") (pin "AC28") (pinfunction "VSS_AC28") (pintype "passive"))
      (node (ref "U1") (pin "AC30") (pinfunction "VSS_AC30") (pintype "passive"))
      (node (ref "U1") (pin "AC32") (pinfunction "VSS_AC32") (pintype "passive"))
      (node (ref "U1") (pin "AC34") (pinfunction "VSS_AC34") (pintype "passive"))
      (node (ref "U1") (pin "AC5") (pinfunction "VSS_AC5") (pintype "passive"))
      (node (ref "U1") (pin "AC7") (pinfunction "VSS_AC7") (pintype "passive"))
      (node (ref "U1") (pin "AC9") (pinfunction "VSS_AC9") (pintype "passive"))
      (node (ref "U1") (pin "AD10") (pinfunction "VSS_AD10") (pintype "passive"))
      (node (ref "U1") (pin "AD12") (pinfunction "VSS_AD12") (pintype "passive"))
      (node (ref "U1") (pin "AD14") (pinfunction "VSS_AD14") (pintype "passive"))
      (node (ref "U1") (pin "AD16") (pinfunction "VSS_AD16") (pintype "passive"))
      (node (ref "U1") (pin "AD18") (pinfunction "VSS_AD18") (pintype "passive"))
      (node (ref "U1") (pin "AD19") (pinfunction "VSS_AD19") (pintype "passive"))
      (node (ref "U1") (pin "AD21") (pinfunction "VSS_AD21") (pintype "passive"))
      (node (ref "U1") (pin "AD23") (pinfunction "VSS_AD23") (pintype "passive"))
      (node (ref "U1") (pin "AD25") (pinfunction "VSS_AD25") (pintype "passive"))
      (node (ref "U1") (pin "AD27") (pinfunction "VSS_AD27") (pintype "passive"))
      (node (ref "U1") (pin "AD29") (pinfunction "VSS_AD29") (pintype "passive"))
      (node (ref "U1") (pin "AD31") (pinfunction "VSS_AD31") (pintype "passive"))
      (node (ref "U1") (pin "AD4") (pinfunction "VSS_AD4") (pintype "passive"))
      (node (ref "U1") (pin "AD6") (pinfunction "VSS_AD6") (pintype "passive"))
      (node (ref "U1") (pin "AD8") (pinfunction "VSS_AD8") (pintype "passive"))
      (node (ref "U1") (pin "AE1") (pinfunction "VSS_AE1") (pintype "passive"))
      (node (ref "U1") (pin "AE11") (pinfunction "VSS_AE11") (pintype "passive"))
      (node (ref "U1") (pin "AE13") (pinfunction "VSS_AE13") (pintype "passive"))
      (node (ref "U1") (pin "AE15") (pinfunction "VSS_AE15") (pintype "passive"))
      (node (ref "U1") (pin "AE17") (pinfunction "VSS_AE17") (pintype "passive"))
      (node (ref "U1") (pin "AE20") (pinfunction "VSS_AE20") (pintype "passive"))
      (node (ref "U1") (pin "AE22") (pinfunction "VSS_AE22") (pintype "passive"))
      (node (ref "U1") (pin "AE24") (pinfunction "VSS_AE24") (pintype "passive"))
      (node (ref "U1") (pin "AE26") (pinfunction "VSS_AE26") (pintype "passive"))
      (node (ref "U1") (pin "AE28") (pinfunction "VSS_AE28") (pintype "passive"))
      (node (ref "U1") (pin "AE30") (pinfunction "VSS_AE30") (pintype "passive"))
      (node (ref "U1") (pin "AE32") (pinfunction "VSS_AE32") (pintype "passive"))
      (node (ref "U1") (pin "AE5") (pinfunction "VSS_AE5") (pintype "passive"))
      (node (ref "U1") (pin "AE7") (pinfunction "VSS_AE7") (pintype "passive"))
      (node (ref "U1") (pin "AE9") (pinfunction "VSS_AE9") (pintype "passive"))
      (node (ref "U1") (pin "AF10") (pinfunction "VSS_AF10") (pintype "passive"))
      (node (ref "U1") (pin "AF12") (pinfunction "VSS_AF12") (pintype "passive"))
      (node (ref "U1") (pin "AF14") (pinfunction "VSS_AF14") (pintype "passive"))
      (node (ref "U1") (pin "AF16") (pinfunction "VSS_AF16") (pintype "passive"))
      (node (ref "U1") (pin "AF18") (pinfunction "VSS_AF18") (pintype "passive"))
      (node (ref "U1") (pin "AF19") (pinfunction "VSS_AF19") (pintype "passive"))
      (node (ref "U1") (pin "AF21") (pinfunction "VSS_AF21") (pintype "passive"))
      (node (ref "U1") (pin "AF23") (pinfunction "VSS_AF23") (pintype "passive"))
      (node (ref "U1") (pin "AF25") (pinfunction "VSS_AF25") (pintype "passive"))
      (node (ref "U1") (pin "AF27") (pinfunction "VSS_AF27") (pintype "passive"))
      (node (ref "U1") (pin "AF29") (pinfunction "VSS_AF29") (pintype "passive"))
      (node (ref "U1") (pin "AF31") (pinfunction "VSS_AF31") (pintype "passive"))
      (node (ref "U1") (pin "AF35") (pinfunction "VSS_AF35") (pintype "passive"))
      (node (ref "U1") (pin "AF8") (pinfunction "VSS_AF8") (pintype "passive"))
      (node (ref "U1") (pin "AG1") (pinfunction "VSS_AG1") (pintype "passive"))
      (node (ref "U1") (pin "AG11") (pinfunction "VSS_AG11") (pintype "passive"))
      (node (ref "U1") (pin "AG13") (pinfunction "VSS_AG13") (pintype "passive"))
      (node (ref "U1") (pin "AG15") (pinfunction "VSS_AG15") (pintype "passive"))
      (node (ref "U1") (pin "AG17") (pinfunction "VSS_AG17") (pintype "passive"))
      (node (ref "U1") (pin "AG20") (pinfunction "VSS_AG20") (pintype "passive"))
      (node (ref "U1") (pin "AG22") (pinfunction "VSS_AG22") (pintype "passive"))
      (node (ref "U1") (pin "AG24") (pinfunction "VSS_AG24") (pintype "passive"))
      (node (ref "U1") (pin "AG26") (pinfunction "VSS_AG26") (pintype "passive"))
      (node (ref "U1") (pin "AG28") (pinfunction "VSS_AG28") (pintype "passive"))
      (node (ref "U1") (pin "AG30") (pinfunction "VSS_AG30") (pintype "passive"))
      (node (ref "U1") (pin "AG32") (pinfunction "VSS_AG32") (pintype "passive"))
      (node (ref "U1") (pin "AG5") (pinfunction "VSS_AG5") (pintype "passive"))
      (node (ref "U1") (pin "AG7") (pinfunction "VSS_AG7") (pintype "passive"))
      (node (ref "U1") (pin "AG9") (pinfunction "VSS_AG9") (pintype "passive"))
      (node (ref "U1") (pin "AH10") (pinfunction "VSS_AH10") (pintype "passive"))
      (node (ref "U1") (pin "AH12") (pinfunction "VSS_AH12") (pintype "passive"))
      (node (ref "U1") (pin "AH14") (pinfunction "VSS_AH14") (pintype "passive"))
      (node (ref "U1") (pin "AH16") (pinfunction "VSS_AH16") (pintype "passive"))
      (node (ref "U1") (pin "AH18") (pinfunction "VSS_AH18") (pintype "passive"))
      (node (ref "U1") (pin "AH19") (pinfunction "VSS_AH19") (pintype "passive"))
      (node (ref "U1") (pin "AH2") (pinfunction "VSS_AH2") (pintype "passive"))
      (node (ref "U1") (pin "AH21") (pinfunction "VSS_AH21") (pintype "passive"))
      (node (ref "U1") (pin "AH23") (pinfunction "VSS_AH23") (pintype "passive"))
      (node (ref "U1") (pin "AH25") (pinfunction "VSS_AH25") (pintype "passive"))
      (node (ref "U1") (pin "AH27") (pinfunction "VSS_AH27") (pintype "passive"))
      (node (ref "U1") (pin "AH29") (pinfunction "VSS_AH29") (pintype "passive"))
      (node (ref "U1") (pin "AH31") (pinfunction "VSS_AH31") (pintype "passive"))
      (node (ref "U1") (pin "AH6") (pinfunction "VSS_AH6") (pintype "passive"))
      (node (ref "U1") (pin "AH8") (pinfunction "VSS_AH8") (pintype "passive"))
      (node (ref "U1") (pin "AJ11") (pinfunction "VSS_AJ11") (pintype "passive"))
      (node (ref "U1") (pin "AJ13") (pinfunction "VSS_AJ13") (pintype "passive"))
      (node (ref "U1") (pin "AJ15") (pinfunction "VSS_AJ15") (pintype "passive"))
      (node (ref "U1") (pin "AJ17") (pinfunction "VSS_AJ17") (pintype "passive"))
      (node (ref "U1") (pin "AJ20") (pinfunction "VSS_AJ20") (pintype "passive"))
      (node (ref "U1") (pin "AJ22") (pinfunction "VSS_AJ22") (pintype "passive"))
      (node (ref "U1") (pin "AJ24") (pinfunction "VSS_AJ24") (pintype "passive"))
      (node (ref "U1") (pin "AJ26") (pinfunction "VSS_AJ26") (pintype "passive"))
      (node (ref "U1") (pin "AJ28") (pinfunction "VSS_AJ28") (pintype "passive"))
      (node (ref "U1") (pin "AJ30") (pinfunction "VSS_AJ30") (pintype "passive"))
      (node (ref "U1") (pin "AJ32") (pinfunction "VSS_AJ32") (pintype "passive"))
      (node (ref "U1") (pin "AJ36") (pinfunction "VSS_AJ36") (pintype "passive"))
      (node (ref "U1") (pin "AJ5") (pinfunction "VSS_AJ5") (pintype "passive"))
      (node (ref "U1") (pin "AJ7") (pinfunction "VSS_AJ7") (pintype "passive"))
      (node (ref "U1") (pin "AJ9") (pinfunction "VSS_AJ9") (pintype "passive"))
      (node (ref "U1") (pin "AK10") (pinfunction "VSS_AK10") (pintype "passive"))
      (node (ref "U1") (pin "AK12") (pinfunction "VSS_AK12") (pintype "passive"))
      (node (ref "U1") (pin "AK14") (pinfunction "VSS_AK14") (pintype "passive"))
      (node (ref "U1") (pin "AK16") (pinfunction "VSS_AK16") (pintype "passive"))
      (node (ref "U1") (pin "AK18") (pinfunction "VSS_AK18") (pintype "passive"))
      (node (ref "U1") (pin "AK19") (pinfunction "VSS_AK19") (pintype "passive"))
      (node (ref "U1") (pin "AK21") (pinfunction "VSS_AK21") (pintype "passive"))
      (node (ref "U1") (pin "AK23") (pinfunction "VSS_AK23") (pintype "passive"))
      (node (ref "U1") (pin "AK25") (pinfunction "VSS_AK25") (pintype "passive"))
      (node (ref "U1") (pin "AK27") (pinfunction "VSS_AK27") (pintype "passive"))
      (node (ref "U1") (pin "AK29") (pinfunction "VSS_AK29") (pintype "passive"))
      (node (ref "U1") (pin "AK31") (pinfunction "VSS_AK31") (pintype "passive"))
      (node (ref "U1") (pin "AK33") (pinfunction "VSS_AK33") (pintype "passive"))
      (node (ref "U1") (pin "AK6") (pinfunction "VSS_AK6") (pintype "passive"))
      (node (ref "U1") (pin "AK8") (pinfunction "VSS_AK8") (pintype "passive"))
      (node (ref "U1") (pin "AL11") (pinfunction "VSS_AL11") (pintype "passive"))
      (node (ref "U1") (pin "AL13") (pinfunction "VSS_AL13") (pintype "passive"))
      (node (ref "U1") (pin "AL15") (pinfunction "VSS_AL15") (pintype "passive"))
      (node (ref "U1") (pin "AL17") (pinfunction "VSS_AL17") (pintype "passive"))
      (node (ref "U1") (pin "AL20") (pinfunction "VSS_AL20") (pintype "passive"))
      (node (ref "U1") (pin "AL22") (pinfunction "VSS_AL22") (pintype "passive"))
      (node (ref "U1") (pin "AL24") (pinfunction "VSS_AL24") (pintype "passive"))
      (node (ref "U1") (pin "AL28") (pinfunction "VSS_AL28") (pintype "passive"))
      (node (ref "U1") (pin "AL3") (pinfunction "VSS_AL3") (pintype "passive"))
      (node (ref "U1") (pin "AL30") (pinfunction "VSS_AL30") (pintype "passive"))
      (node (ref "U1") (pin "AL5") (pinfunction "VSS_AL5") (pintype "passive"))
      (node (ref "U1") (pin "AL7") (pinfunction "VSS_AL7") (pintype "passive"))
      (node (ref "U1") (pin "AL9") (pinfunction "VSS_AL9") (pintype "passive"))
      (node (ref "U1") (pin "AM10") (pinfunction "VSS_AM10") (pintype "passive"))
      (node (ref "U1") (pin "AM12") (pinfunction "VSS_AM12") (pintype "passive"))
      (node (ref "U1") (pin "AM14") (pinfunction "VSS_AM14") (pintype "passive"))
      (node (ref "U1") (pin "AM16") (pinfunction "VSS_AM16") (pintype "passive"))
      (node (ref "U1") (pin "AM18") (pinfunction "VSS_AM18") (pintype "passive"))
      (node (ref "U1") (pin "AM20") (pinfunction "VSS_AM20") (pintype "passive"))
      (node (ref "U1") (pin "AM21") (pinfunction "VSS_AM21") (pintype "passive"))
      (node (ref "U1") (pin "AM23") (pinfunction "VSS_AM23") (pintype "passive"))
      (node (ref "U1") (pin "AM25") (pinfunction "VSS_AM25") (pintype "passive"))
      (node (ref "U1") (pin "AM27") (pinfunction "VSS_AM27") (pintype "passive"))
      (node (ref "U1") (pin "AM29") (pinfunction "VSS_AM29") (pintype "passive"))
      (node (ref "U1") (pin "AM31") (pinfunction "VSS_AM31") (pintype "passive"))
      (node (ref "U1") (pin "AM35") (pinfunction "VSS_AM35") (pintype "passive"))
      (node (ref "U1") (pin "AM8") (pinfunction "VSS_AM8") (pintype "passive"))
      (node (ref "U1") (pin "AN17") (pinfunction "VSS_AN17") (pintype "passive"))
      (node (ref "U1") (pin "AN24") (pinfunction "VSS_AN24") (pintype "passive"))
      (node (ref "U1") (pin "AN34") (pinfunction "VSS_AN34") (pintype "passive"))
      (node (ref "U1") (pin "AN7") (pinfunction "VSS_AN7") (pintype "passive"))
      (node (ref "U1") (pin "AP14") (pinfunction "VSS_AP14") (pintype "passive"))
      (node (ref "U1") (pin "AP18") (pinfunction "VSS_AP18") (pintype "passive"))
      (node (ref "U1") (pin "AP21") (pinfunction "VSS_AP21") (pintype "passive"))
      (node (ref "U1") (pin "AP31") (pinfunction "VSS_AP31") (pintype "passive"))
      (node (ref "U1") (pin "AP4") (pinfunction "VSS_AP4") (pintype "passive"))
      (node (ref "U1") (pin "AR1") (pinfunction "VSS_AR1") (pintype "passive"))
      (node (ref "U1") (pin "AR11") (pinfunction "VSS_AR11") (pintype "passive"))
      (node (ref "U1") (pin "AR28") (pinfunction "VSS_AR28") (pintype "passive"))
      (node (ref "U1") (pin "AR36") (pinfunction "VSS_AR36") (pintype "passive"))
      (node (ref "U1") (pin "AR5") (pinfunction "VSS_AR5") (pintype "passive"))
      (node (ref "U1") (pin "AT1") (pinfunction "VSS_AT1") (pintype "passive"))
      (node (ref "U1") (pin "AT18") (pinfunction "VSS_AT18") (pintype "passive"))
      (node (ref "U1") (pin "AT2") (pinfunction "VSS_AT2") (pintype "passive"))
      (node (ref "U1") (pin "AT25") (pinfunction "VSS_AT25") (pintype "passive"))
      (node (ref "U1") (pin "AT27") (pinfunction "VSS_AT27") (pintype "passive"))
      (node (ref "U1") (pin "AT35") (pinfunction "VSS_AT35") (pintype "passive"))
      (node (ref "U1") (pin "AT36") (pinfunction "VSS_AT36") (pintype "passive"))
      (node (ref "U1") (pin "AT8") (pinfunction "VSS_AT8") (pintype "passive"))
      (node (ref "U1") (pin "B1") (pinfunction "VSS_B1") (pintype "passive"))
      (node (ref "U1") (pin "B26") (pinfunction "VSS_B26") (pintype "passive"))
      (node (ref "U1") (pin "B32") (pinfunction "VSS_B32") (pintype "passive"))
      (node (ref "U1") (pin "B36") (pinfunction "VSS_B36") (pintype "passive"))
      (node (ref "U1") (pin "B9") (pinfunction "VSS_B9") (pintype "passive"))
      (node (ref "U1") (pin "C16") (pinfunction "VSS_C16") (pintype "passive"))
      (node (ref "U1") (pin "C19") (pinfunction "VSS_C19") (pintype "passive"))
      (node (ref "U1") (pin "C23") (pinfunction "VSS_C23") (pintype "passive"))
      (node (ref "U1") (pin "C33") (pinfunction "VSS_C33") (pintype "passive"))
      (node (ref "U1") (pin "C6") (pinfunction "VSS_C6") (pintype "passive"))
      (node (ref "U1") (pin "D13") (pinfunction "VSS_D13") (pintype "passive"))
      (node (ref "U1") (pin "D20") (pinfunction "VSS_D20") (pintype "passive"))
      (node (ref "U1") (pin "D3") (pinfunction "VSS_D3") (pintype "passive"))
      (node (ref "U1") (pin "D30") (pinfunction "VSS_D30") (pintype "passive"))
      (node (ref "U1") (pin "E10") (pinfunction "VSS_E10") (pintype "passive"))
      (node (ref "U1") (pin "E12") (pinfunction "VSS_E12") (pintype "passive"))
      (node (ref "U1") (pin "E14") (pinfunction "VSS_E14") (pintype "passive"))
      (node (ref "U1") (pin "E16") (pinfunction "VSS_E16") (pintype "passive"))
      (node (ref "U1") (pin "E17") (pinfunction "VSS_E17") (pintype "passive"))
      (node (ref "U1") (pin "E19") (pinfunction "VSS_E19") (pintype "passive"))
      (node (ref "U1") (pin "E2") (pinfunction "VSS_E2") (pintype "passive"))
      (node (ref "U1") (pin "E21") (pinfunction "VSS_E21") (pintype "passive"))
      (node (ref "U1") (pin "E23") (pinfunction "VSS_E23") (pintype "passive"))
      (node (ref "U1") (pin "E25") (pinfunction "VSS_E25") (pintype "passive"))
      (node (ref "U1") (pin "E27") (pinfunction "VSS_E27") (pintype "passive"))
      (node (ref "U1") (pin "E29") (pinfunction "VSS_E29") (pintype "passive"))
      (node (ref "U1") (pin "E6") (pinfunction "VSS_E6") (pintype "passive"))
      (node (ref "U1") (pin "E8") (pinfunction "VSS_E8") (pintype "passive"))
      (node (ref "U1") (pin "F13") (pinfunction "VSS_F13") (pintype "passive"))
      (node (ref "U1") (pin "F15") (pinfunction "VSS_F15") (pintype "passive"))
      (node (ref "U1") (pin "F17") (pinfunction "VSS_F17") (pintype "passive"))
      (node (ref "U1") (pin "F20") (pinfunction "VSS_F20") (pintype "passive"))
      (node (ref "U1") (pin "F22") (pinfunction "VSS_F22") (pintype "passive"))
      (node (ref "U1") (pin "F24") (pinfunction "VSS_F24") (pintype "passive"))
      (node (ref "U1") (pin "F26") (pinfunction "VSS_F26") (pintype "passive"))
      (node (ref "U1") (pin "F28") (pinfunction "VSS_F28") (pintype "passive"))
      (node (ref "U1") (pin "F30") (pinfunction "VSS_F30") (pintype "passive"))
      (node (ref "U1") (pin "F32") (pinfunction "VSS_F32") (pintype "passive"))
      (node (ref "U1") (pin "F34") (pinfunction "VSS_F34") (pintype "passive"))
      (node (ref "U1") (pin "F7") (pinfunction "VSS_F7") (pintype "passive"))
      (node (ref "U1") (pin "F9") (pinfunction "VSS_F9") (pintype "passive"))
      (node (ref "U1") (pin "G10") (pinfunction "VSS_G10") (pintype "passive"))
      (node (ref "U1") (pin "G12") (pinfunction "VSS_G12") (pintype "passive"))
      (node (ref "U1") (pin "G14") (pinfunction "VSS_G14") (pintype "passive"))
      (node (ref "U1") (pin "G16") (pinfunction "VSS_G16") (pintype "passive"))
      (node (ref "U1") (pin "G18") (pinfunction "VSS_G18") (pintype "passive"))
      (node (ref "U1") (pin "G19") (pinfunction "VSS_G19") (pintype "passive"))
      (node (ref "U1") (pin "G21") (pinfunction "VSS_G21") (pintype "passive"))
      (node (ref "U1") (pin "G23") (pinfunction "VSS_G23") (pintype "passive"))
      (node (ref "U1") (pin "G25") (pinfunction "VSS_G25") (pintype "passive"))
      (node (ref "U1") (pin "G27") (pinfunction "VSS_G27") (pintype "passive"))
      (node (ref "U1") (pin "G29") (pinfunction "VSS_G29") (pintype "passive"))
      (node (ref "U1") (pin "G31") (pinfunction "VSS_G31") (pintype "passive"))
      (node (ref "U1") (pin "G4") (pinfunction "VSS_G4") (pintype "passive"))
      (node (ref "U1") (pin "G6") (pinfunction "VSS_G6") (pintype "passive"))
      (node (ref "U1") (pin "G8") (pinfunction "VSS_G8") (pintype "passive"))
      (node (ref "U1") (pin "H1") (pinfunction "VSS_H1") (pintype "passive"))
      (node (ref "U1") (pin "H11") (pinfunction "VSS_H11") (pintype "passive"))
      (node (ref "U1") (pin "H13") (pinfunction "VSS_H13") (pintype "passive"))
      (node (ref "U1") (pin "H15") (pinfunction "VSS_H15") (pintype "passive"))
      (node (ref "U1") (pin "H17") (pinfunction "VSS_H17") (pintype "passive"))
      (node (ref "U1") (pin "H20") (pinfunction "VSS_H20") (pintype "passive"))
      (node (ref "U1") (pin "H22") (pinfunction "VSS_H22") (pintype "passive"))
      (node (ref "U1") (pin "H24") (pinfunction "VSS_H24") (pintype "passive"))
      (node (ref "U1") (pin "H26") (pinfunction "VSS_H26") (pintype "passive"))
      (node (ref "U1") (pin "H28") (pinfunction "VSS_H28") (pintype "passive"))
      (node (ref "U1") (pin "H30") (pinfunction "VSS_H30") (pintype "passive"))
      (node (ref "U1") (pin "H32") (pinfunction "VSS_H32") (pintype "passive"))
      (node (ref "U1") (pin "H5") (pinfunction "VSS_H5") (pintype "passive"))
      (node (ref "U1") (pin "H7") (pinfunction "VSS_H7") (pintype "passive"))
      (node (ref "U1") (pin "H9") (pinfunction "VSS_H9") (pintype "passive"))
      (node (ref "U1") (pin "J10") (pinfunction "VSS_J10") (pintype "passive"))
      (node (ref "U1") (pin "J12") (pinfunction "VSS_J12") (pintype "passive"))
      (node (ref "U1") (pin "J14") (pinfunction "VSS_J14") (pintype "passive"))
      (node (ref "U1") (pin "J16") (pinfunction "VSS_J16") (pintype "passive"))
      (node (ref "U1") (pin "J18") (pinfunction "VSS_J18") (pintype "passive"))
      (node (ref "U1") (pin "J19") (pinfunction "VSS_J19") (pintype "passive"))
      (node (ref "U1") (pin "J21") (pinfunction "VSS_J21") (pintype "passive"))
      (node (ref "U1") (pin "J23") (pinfunction "VSS_J23") (pintype "passive"))
      (node (ref "U1") (pin "J25") (pinfunction "VSS_J25") (pintype "passive"))
      (node (ref "U1") (pin "J27") (pinfunction "VSS_J27") (pintype "passive"))
      (node (ref "U1") (pin "J29") (pinfunction "VSS_J29") (pintype "passive"))
      (node (ref "U1") (pin "J31") (pinfunction "VSS_J31") (pintype "passive"))
      (node (ref "U1") (pin "J35") (pinfunction "VSS_J35") (pintype "passive"))
      (node (ref "U1") (pin "J6") (pinfunction "VSS_J6") (pintype "passive"))
      (node (ref "U1") (pin "J8") (pinfunction "VSS_J8") (pintype "passive"))
      (node (ref "U1") (pin "K11") (pinfunction "VSS_K11") (pintype "passive"))
      (node (ref "U1") (pin "K13") (pinfunction "VSS_K13") (pintype "passive"))
      (node (ref "U1") (pin "K15") (pinfunction "VSS_K15") (pintype "passive"))
      (node (ref "U1") (pin "K17") (pinfunction "VSS_K17") (pintype "passive"))
      (node (ref "U1") (pin "K20") (pinfunction "VSS_K20") (pintype "passive"))
      (node (ref "U1") (pin "K22") (pinfunction "VSS_K22") (pintype "passive"))
      (node (ref "U1") (pin "K24") (pinfunction "VSS_K24") (pintype "passive"))
      (node (ref "U1") (pin "K26") (pinfunction "VSS_K26") (pintype "passive"))
      (node (ref "U1") (pin "K28") (pinfunction "VSS_K28") (pintype "passive"))
      (node (ref "U1") (pin "K30") (pinfunction "VSS_K30") (pintype "passive"))
      (node (ref "U1") (pin "K32") (pinfunction "VSS_K32") (pintype "passive"))
      (node (ref "U1") (pin "K36") (pinfunction "VSS_K36") (pintype "passive"))
      (node (ref "U1") (pin "K5") (pinfunction "VSS_K5") (pintype "passive"))
      (node (ref "U1") (pin "K7") (pinfunction "VSS_K7") (pintype "passive"))
      (node (ref "U1") (pin "K9") (pinfunction "VSS_K9") (pintype "passive"))
      (node (ref "U1") (pin "L10") (pinfunction "VSS_L10") (pintype "passive"))
      (node (ref "U1") (pin "L12") (pinfunction "VSS_L12") (pintype "passive"))
      (node (ref "U1") (pin "L14") (pinfunction "VSS_L14") (pintype "passive"))
      (node (ref "U1") (pin "L16") (pinfunction "VSS_L16") (pintype "passive"))
      (node (ref "U1") (pin "L18") (pinfunction "VSS_L18") (pintype "passive"))
      (node (ref "U1") (pin "L19") (pinfunction "VSS_L19") (pintype "passive"))
      (node (ref "U1") (pin "L2") (pinfunction "VSS_L2") (pintype "passive"))
      (node (ref "U1") (pin "L21") (pinfunction "VSS_L21") (pintype "passive"))
      (node (ref "U1") (pin "L23") (pinfunction "VSS_L23") (pintype "passive"))
      (node (ref "U1") (pin "L25") (pinfunction "VSS_L25") (pintype "passive"))
      (node (ref "U1") (pin "L27") (pinfunction "VSS_L27") (pintype "passive"))
      (node (ref "U1") (pin "L29") (pinfunction "VSS_L29") (pintype "passive"))
      (node (ref "U1") (pin "L6") (pinfunction "VSS_L6") (pintype "passive"))
      (node (ref "U1") (pin "L8") (pinfunction "VSS_L8") (pintype "passive"))
      (node (ref "U1") (pin "M11") (pinfunction "VSS_M11") (pintype "passive"))
      (node (ref "U1") (pin "M13") (pinfunction "VSS_M13") (pintype "passive"))
      (node (ref "U1") (pin "M15") (pinfunction "VSS_M15") (pintype "passive"))
      (node (ref "U1") (pin "M17") (pinfunction "VSS_M17") (pintype "passive"))
      (node (ref "U1") (pin "M20") (pinfunction "VSS_M20") (pintype "passive"))
      (node (ref "U1") (pin "M22") (pinfunction "VSS_M22") (pintype "passive"))
      (node (ref "U1") (pin "M24") (pinfunction "VSS_M24") (pintype "passive"))
      (node (ref "U1") (pin "M26") (pinfunction "VSS_M26") (pintype "passive"))
      (node (ref "U1") (pin "M28") (pinfunction "VSS_M28") (pintype "passive"))
      (node (ref "U1") (pin "M30") (pinfunction "VSS_M30") (pintype "passive"))
      (node (ref "U1") (pin "M32") (pinfunction "VSS_M32") (pintype "passive"))
      (node (ref "U1") (pin "M36") (pinfunction "VSS_M36") (pintype "passive"))
      (node (ref "U1") (pin "M5") (pinfunction "VSS_M5") (pintype "passive"))
      (node (ref "U1") (pin "M7") (pinfunction "VSS_M7") (pintype "passive"))
      (node (ref "U1") (pin "M9") (pinfunction "VSS_M9") (pintype "passive"))
      (node (ref "U1") (pin "N10") (pinfunction "VSS_N10") (pintype "passive"))
      (node (ref "U1") (pin "N12") (pinfunction "VSS_N12") (pintype "passive"))
      (node (ref "U1") (pin "N14") (pinfunction "VSS_N14") (pintype "passive"))
      (node (ref "U1") (pin "N16") (pinfunction "VSS_N16") (pintype "passive"))
      (node (ref "U1") (pin "N18") (pinfunction "VSS_N18") (pintype "passive"))
      (node (ref "U1") (pin "N19") (pinfunction "VSS_N19") (pintype "passive"))
      (node (ref "U1") (pin "N21") (pinfunction "VSS_N21") (pintype "passive"))
      (node (ref "U1") (pin "N23") (pinfunction "VSS_N23") (pintype "passive"))
      (node (ref "U1") (pin "N25") (pinfunction "VSS_N25") (pintype "passive"))
      (node (ref "U1") (pin "N27") (pinfunction "VSS_N27") (pintype "passive"))
      (node (ref "U1") (pin "N29") (pinfunction "VSS_N29") (pintype "passive"))
      (node (ref "U1") (pin "N31") (pinfunction "VSS_N31") (pintype "passive"))
      (node (ref "U1") (pin "N33") (pinfunction "VSS_N33") (pintype "passive"))
      (node (ref "U1") (pin "N6") (pinfunction "VSS_N6") (pintype "passive"))
      (node (ref "U1") (pin "N8") (pinfunction "VSS_N8") (pintype "passive"))
      (node (ref "U1") (pin "P11") (pinfunction "VSS_P11") (pintype "passive"))
      (node (ref "U1") (pin "P13") (pinfunction "VSS_P13") (pintype "passive"))
      (node (ref "U1") (pin "P15") (pinfunction "VSS_P15") (pintype "passive"))
      (node (ref "U1") (pin "P17") (pinfunction "VSS_P17") (pintype "passive"))
      (node (ref "U1") (pin "P20") (pinfunction "VSS_P20") (pintype "passive"))
      (node (ref "U1") (pin "P22") (pinfunction "VSS_P22") (pintype "passive"))
      (node (ref "U1") (pin "P24") (pinfunction "VSS_P24") (pintype "passive"))
      (node (ref "U1") (pin "P26") (pinfunction "VSS_P26") (pintype "passive"))
      (node (ref "U1") (pin "P28") (pinfunction "VSS_P28") (pintype "passive"))
      (node (ref "U1") (pin "P3") (pinfunction "VSS_P3") (pintype "passive"))
      (node (ref "U1") (pin "P30") (pinfunction "VSS_P30") (pintype "passive"))
      (node (ref "U1") (pin "P32") (pinfunction "VSS_P32") (pintype "passive"))
      (node (ref "U1") (pin "P5") (pinfunction "VSS_P5") (pintype "passive"))
      (node (ref "U1") (pin "P7") (pinfunction "VSS_P7") (pintype "passive"))
      (node (ref "U1") (pin "P9") (pinfunction "VSS_P9") (pintype "passive"))
      (node (ref "U1") (pin "R10") (pinfunction "VSS_R10") (pintype "passive"))
      (node (ref "U1") (pin "R12") (pinfunction "VSS_R12") (pintype "passive"))
      (node (ref "U1") (pin "R14") (pinfunction "VSS_R14") (pintype "passive"))
      (node (ref "U1") (pin "R16") (pinfunction "VSS_R16") (pintype "passive"))
      (node (ref "U1") (pin "R18") (pinfunction "VSS_R18") (pintype "passive"))
      (node (ref "U1") (pin "R19") (pinfunction "VSS_R19") (pintype "passive"))
      (node (ref "U1") (pin "R21") (pinfunction "VSS_R21") (pintype "passive"))
      (node (ref "U1") (pin "R23") (pinfunction "VSS_R23") (pintype "passive"))
      (node (ref "U1") (pin "R25") (pinfunction "VSS_R25") (pintype "passive"))
      (node (ref "U1") (pin "R27") (pinfunction "VSS_R27") (pintype "passive"))
      (node (ref "U1") (pin "R29") (pinfunction "VSS_R29") (pintype "passive"))
      (node (ref "U1") (pin "R31") (pinfunction "VSS_R31") (pintype "passive"))
      (node (ref "U1") (pin "R6") (pinfunction "VSS_R6") (pintype "passive"))
      (node (ref "U1") (pin "R8") (pinfunction "VSS_R8") (pintype "passive"))
      (node (ref "U1") (pin "T11") (pinfunction "VSS_T11") (pintype "passive"))
      (node (ref "U1") (pin "T13") (pinfunction "VSS_T13") (pintype "passive"))
      (node (ref "U1") (pin "T15") (pinfunction "VSS_T15") (pintype "passive"))
      (node (ref "U1") (pin "T17") (pinfunction "VSS_T17") (pintype "passive"))
      (node (ref "U1") (pin "T20") (pinfunction "VSS_T20") (pintype "passive"))
      (node (ref "U1") (pin "T22") (pinfunction "VSS_T22") (pintype "passive"))
      (node (ref "U1") (pin "T24") (pinfunction "VSS_T24") (pintype "passive"))
      (node (ref "U1") (pin "T26") (pinfunction "VSS_T26") (pintype "passive"))
      (node (ref "U1") (pin "T28") (pinfunction "VSS_T28") (pintype "passive"))
      (node (ref "U1") (pin "T30") (pinfunction "VSS_T30") (pintype "passive"))
      (node (ref "U1") (pin "T32") (pinfunction "VSS_T32") (pintype "passive"))
      (node (ref "U1") (pin "T34") (pinfunction "VSS_T34") (pintype "passive"))
      (node (ref "U1") (pin "T5") (pinfunction "VSS_T5") (pintype "passive"))
      (node (ref "U1") (pin "T7") (pinfunction "VSS_T7") (pintype "passive"))
      (node (ref "U1") (pin "T9") (pinfunction "VSS_T9") (pintype "passive"))
      (node (ref "U1") (pin "U10") (pinfunction "VSS_U10") (pintype "passive"))
      (node (ref "U1") (pin "U12") (pinfunction "VSS_U12") (pintype "passive"))
      (node (ref "U1") (pin "U14") (pinfunction "VSS_U14") (pintype "passive"))
      (node (ref "U1") (pin "U16") (pinfunction "VSS_U16") (pintype "passive"))
      (node (ref "U1") (pin "U18") (pinfunction "VSS_U18") (pintype "passive"))
      (node (ref "U1") (pin "U19") (pinfunction "VSS_U19") (pintype "passive"))
      (node (ref "U1") (pin "U21") (pinfunction "VSS_U21") (pintype "passive"))
      (node (ref "U1") (pin "U23") (pinfunction "VSS_U23") (pintype "passive"))
      (node (ref "U1") (pin "U25") (pinfunction "VSS_U25") (pintype "passive"))
      (node (ref "U1") (pin "U27") (pinfunction "VSS_U27") (pintype "passive"))
      (node (ref "U1") (pin "U29") (pinfunction "VSS_U29") (pintype "passive"))
      (node (ref "U1") (pin "U31") (pinfunction "VSS_U31") (pintype "passive"))
      (node (ref "U1") (pin "U32") (pinfunction "VSS_U32") (pintype "passive"))
      (node (ref "U1") (pin "U4") (pinfunction "VSS_U4") (pintype "passive"))
      (node (ref "U1") (pin "U6") (pinfunction "VSS_U6") (pintype "passive"))
      (node (ref "U1") (pin "U8") (pinfunction "VSS_U8") (pintype "passive"))
      (node (ref "U1") (pin "V1") (pinfunction "VSS_V1") (pintype "passive"))
      (node (ref "U1") (pin "V11") (pinfunction "VSS_V11") (pintype "passive"))
      (node (ref "U1") (pin "V13") (pinfunction "VSS_V13") (pintype "passive"))
      (node (ref "U1") (pin "V15") (pinfunction "VSS_V15") (pintype "passive"))
      (node (ref "U1") (pin "V17") (pinfunction "VSS_V17") (pintype "passive"))
      (node (ref "U1") (pin "V20") (pinfunction "VSS_V20") (pintype "passive"))
      (node (ref "U1") (pin "V22") (pinfunction "VSS_V22") (pintype "passive"))
      (node (ref "U1") (pin "V24") (pinfunction "VSS_V24") (pintype "passive"))
      (node (ref "U1") (pin "V26") (pinfunction "VSS_V26") (pintype "passive"))
      (node (ref "U1") (pin "V28") (pinfunction "VSS_V28") (pintype "passive"))
      (node (ref "U1") (pin "V3") (pinfunction "VSS_V3") (pintype "passive"))
      (node (ref "U1") (pin "V30") (pinfunction "VSS_V30") (pintype "passive"))
      (node (ref "U1") (pin "V5") (pinfunction "VSS_V5") (pintype "passive"))
      (node (ref "U1") (pin "V7") (pinfunction "VSS_V7") (pintype "passive"))
      (node (ref "U1") (pin "V9") (pinfunction "VSS_V9") (pintype "passive"))
      (node (ref "U1") (pin "W11") (pinfunction "VSS_W11") (pintype "passive"))
      (node (ref "U1") (pin "W13") (pinfunction "VSS_W13") (pintype "passive"))
      (node (ref "U1") (pin "W15") (pinfunction "VSS_W15") (pintype "passive"))
      (node (ref "U1") (pin "W17") (pinfunction "VSS_W17") (pintype "passive"))
      (node (ref "U1") (pin "W20") (pinfunction "VSS_W20") (pintype "passive"))
      (node (ref "U1") (pin "W22") (pinfunction "VSS_W22") (pintype "passive"))
      (node (ref "U1") (pin "W24") (pinfunction "VSS_W24") (pintype "passive"))
      (node (ref "U1") (pin "W26") (pinfunction "VSS_W26") (pintype "passive"))
      (node (ref "U1") (pin "W28") (pinfunction "VSS_W28") (pintype "passive"))
      (node (ref "U1") (pin "W30") (pinfunction "VSS_W30") (pintype "passive"))
      (node (ref "U1") (pin "W32") (pinfunction "VSS_W32") (pintype "passive"))
      (node (ref "U1") (pin "W34") (pinfunction "VSS_W34") (pintype "passive"))
      (node (ref "U1") (pin "W36") (pinfunction "VSS_W36") (pintype "passive"))
      (node (ref "U1") (pin "W7") (pinfunction "VSS_W7") (pintype "passive"))
      (node (ref "U1") (pin "W9") (pinfunction "VSS_W9") (pintype "passive"))
      (node (ref "U1") (pin "Y10") (pinfunction "VSS_Y10") (pintype "passive"))
      (node (ref "U1") (pin "Y12") (pinfunction "VSS_Y12") (pintype "passive"))
      (node (ref "U1") (pin "Y14") (pinfunction "VSS_Y14") (pintype "passive"))
      (node (ref "U1") (pin "Y16") (pinfunction "VSS_Y16") (pintype "passive"))
      (node (ref "U1") (pin "Y18") (pinfunction "VSS_Y18") (pintype "passive"))
      (node (ref "U1") (pin "Y19") (pinfunction "VSS_Y19") (pintype "passive"))
      (node (ref "U1") (pin "Y21") (pinfunction "VSS_Y21") (pintype "passive"))
      (node (ref "U1") (pin "Y23") (pinfunction "VSS_Y23") (pintype "passive"))
      (node (ref "U1") (pin "Y25") (pinfunction "VSS_Y25") (pintype "passive"))
      (node (ref "U1") (pin "Y27") (pinfunction "VSS_Y27") (pintype "passive"))
      (node (ref "U1") (pin "Y29") (pinfunction "VSS_Y29") (pintype "passive"))
      (node (ref "U1") (pin "Y31") (pinfunction "VSS_Y31") (pintype "passive"))
      (node (ref "U1") (pin "Y33") (pinfunction "VSS_Y33") (pintype "passive"))
      (node (ref "U1") (pin "Y5") (pinfunction "VSS_Y5") (pintype "passive"))
      (node (ref "U1") (pin "Y6") (pinfunction "VSS_Y6") (pintype "passive"))
      (node (ref "U1") (pin "Y8") (pinfunction "VSS_Y8") (pintype "passive"))
    )
  )
)
